# PowerSupply.net
KiCad netlist of a schematic drawn in Altium Designer
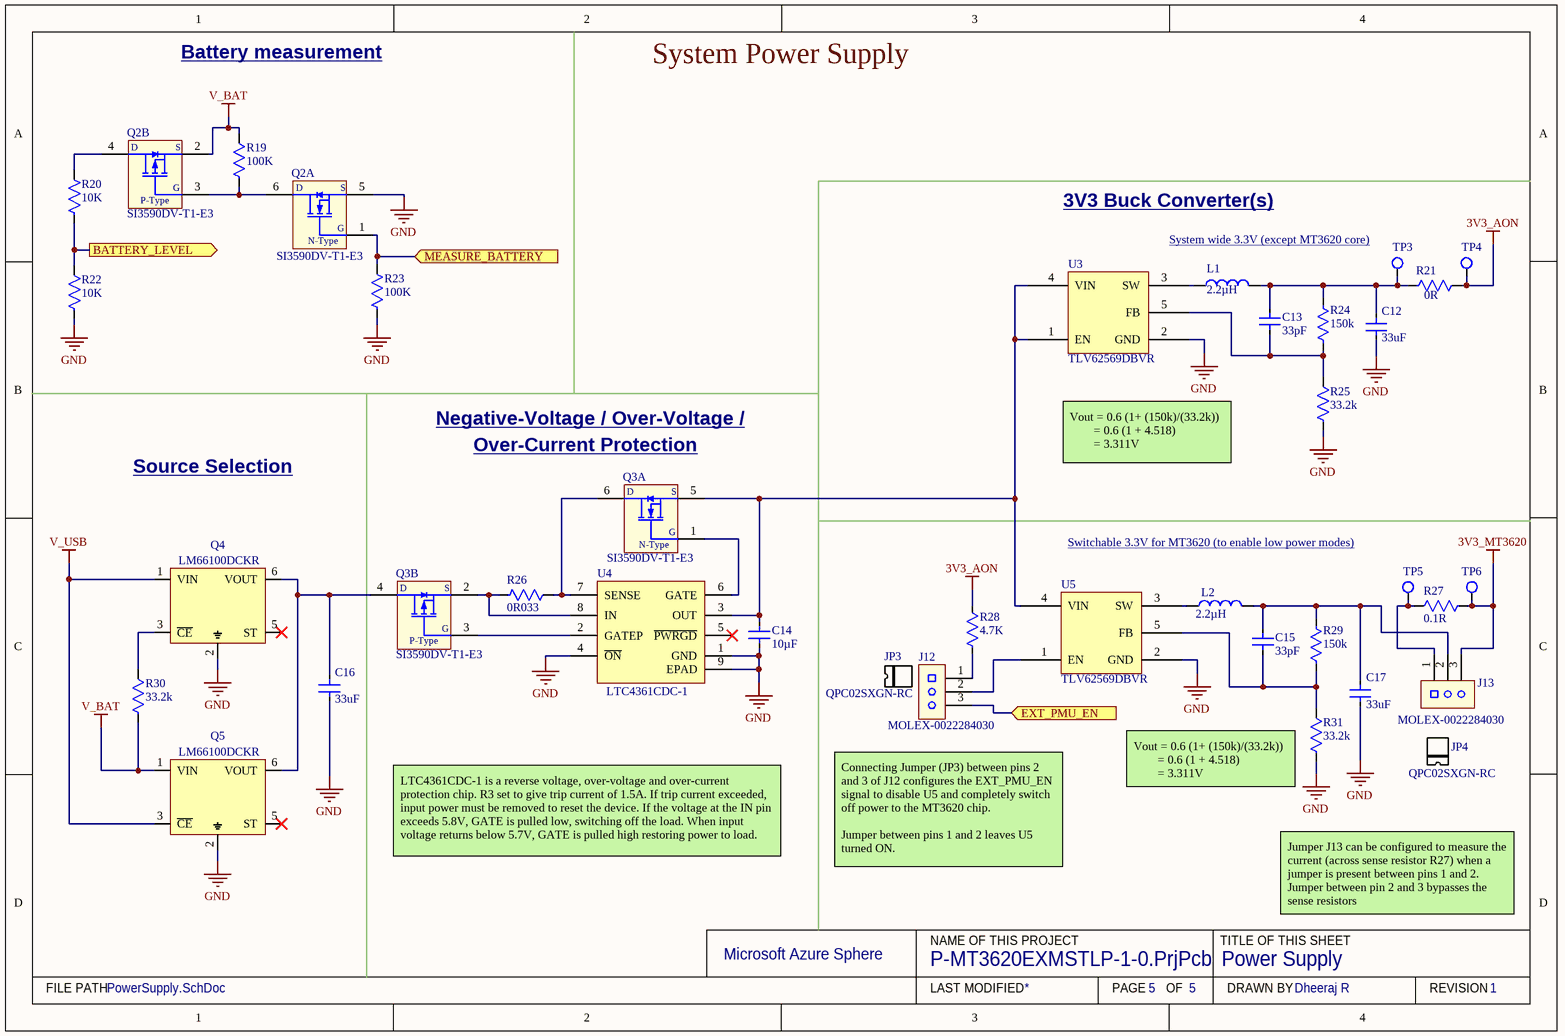
[diagram p0: PowerSupply.SchDoc]

(export (version "E")
  (design (tool "Eeschema 10.0.6"))
  (components
    (comp (ref "C12")
      (value "33uF")
      (footprint "TDK_0805")
      (description "CAP CER 33UF 10V X5R 0805")
      (fields
        (field (name "MANUFACTURER") "TDK")
        (field (name "MANUFACTURER PART NUMBER") "C2012X5R1A336M125AC")
      )
      (libsource (lib "TDK_Capacitor_C_0805") (part "33uF 0805 X5R 10V"))
    )
    (comp (ref "C13")
      (value "33pF")
      (footprint "0603_AVX")
      (fields
        (field (name "MANUFACTURER") "Kyocera AVX")
        (field (name "MANUFACTURER PART NUMBER") "0603YC330JAT2A")
        (field (name "TOLERANCE") "5%")
      )
      (libsource (lib "AVX") (part "0603YC330JAT2A"))
    )
    (comp (ref "C14")
      (value "10µF")
      (footprint "CAPC1608-EIA0603-1MM-MED")
      (description "CAP CER 10UF 25V 20% X5R 0603")
      (fields
        (field (name "MANUFACTURER") "TDK Corporation")
        (field (name "MANUFACTURER PART NUMBER") "C1608X5R1E106M080AC")
        (field (name "CAPACITANCE") "10µF")
      )
      (libsource (lib "TDK-Capacitor_C_0603") (part "10µF 0603 X5R 25V"))
    )
    (comp (ref "C15")
      (value "33pF")
      (footprint "0603_AVX")
      (fields
        (field (name "MANUFACTURER") "Kyocera AVX")
        (field (name "MANUFACTURER PART NUMBER") "0603YC330JAT2A")
        (field (name "TOLERANCE") "5%")
      )
      (libsource (lib "AVX") (part "0603YC330JAT2A"))
    )
    (comp (ref "C16")
      (value "33uF")
      (footprint "TDK_0805")
      (description "CAP CER 33UF 10V X5R 0805")
      (fields
        (field (name "MANUFACTURER") "TDK")
        (field (name "MANUFACTURER PART NUMBER") "C2012X5R1A336M125AC")
      )
      (libsource (lib "TDK_Capacitor_C_0805") (part "33uF 0805 X5R 10V"))
    )
    (comp (ref "C17")
      (value "33uF")
      (footprint "TDK_0805")
      (description "CAP CER 33UF 10V X5R 0805")
      (fields
        (field (name "MANUFACTURER") "TDK")
        (field (name "MANUFACTURER PART NUMBER") "C2012X5R1A336M125AC")
      )
      (libsource (lib "TDK_Capacitor_C_0805") (part "33uF 0805 X5R 10V"))
    )
    (comp (ref "J12")
      (value "MOLEX-0022284030")
      (footprint "0022284030")
      (description "CONN HEADER 3POS .100 VERT TIN")
      (fields
        (field (name "MANUFACTURER") "Molex, LLC")
        (field (name "MANUFACTURER PART NUMBER") "0022284030")
      )
      (libsource (lib "") (part "MOLEX-0022284030_1"))
    )
    (comp (ref "J13")
      (value "MOLEX-0022284030")
      (footprint "0022284030")
      (description "CONN HEADER 3POS .100 VERT TIN")
      (fields
        (field (name "MANUFACTURER") "Molex, LLC")
        (field (name "MANUFACTURER PART NUMBER") "0022284030")
      )
      (libsource (lib "Molex") (part "MOLEX-0022284030"))
    )
    (comp (ref "JP3")
      (value "QPC02SXGN-RC")
      (description "CONN JUMPER SHORTING .100\" GOLD")
      (fields (field (name "MANUFACTURER") "Sullins"))
      (libsource (lib "SullinsConnectorSolutions") (part "QPC02SXGN-RC"))
    )
    (comp (ref "JP4")
      (value "QPC02SXGN-RC")
      (description "CONN JUMPER SHORTING .100\" GOLD")
      (fields (field (name "MANUFACTURER") "Sullins"))
      (libsource (lib "SullinsConnectorSolutions") (part "QPC02SXGN-RC"))
    )
    (comp (ref "L1")
      (value "2.2µH")
      (footprint "NR3015T2R2M")
      (description "FIXED IND 2.2UH 1.5A 72 MOHM SMD")
      (fields
        (field (name "MANUFACTURER") "Taiyo Yuden")
        (field (name "MANUFACTURER PART NUMBER") "NR3015T2R2M")
      )
      (libsource (lib "TaiyoYuden ") (part "NR3015T2R2M"))
    )
    (comp (ref "L2")
      (value "2.2µH")
      (footprint "NR3015T2R2M")
      (description "FIXED IND 2.2UH 1.5A 72 MOHM SMD")
      (fields
        (field (name "MANUFACTURER") "Taiyo Yuden")
        (field (name "MANUFACTURER PART NUMBER") "NR3015T2R2M")
      )
      (libsource (lib "TaiyoYuden ") (part "NR3015T2R2M"))
    )
    (comp (ref "Q2")
      (value "SI3590DV-T1-E3")
      (footprint "SI3590DV-T1-E3")
      (description "MOSFET N&P-CH 30V (D-S)")
      (fields (field (name "MANUFACTURER") "Vishay Siliconix"))
      (libsource (lib "Vishay") (part "SI3590DV-T1-E3"))
    )
    (comp (ref "Q3")
      (value "SI3590DV-T1-E3")
      (footprint "SI3590DV-T1-E3")
      (description "MOSFET N&P-CH 30V (D-S)")
      (fields (field (name "MANUFACTURER") "Vishay Siliconix"))
      (libsource (lib "Vishay") (part "SI3590DV-T1-E3"))
    )
    (comp (ref "Q4")
      (value "LM66100DCKR")
      (footprint "TI-LM6610-SC-70")
      (description "1.5-V to 5.5-V, 1.5-A, 0.5-uA IQ ideal diode with Integrated FET 6-SC70 -40 to 105")
      (fields (field (name "MANUFACTURER") "Texas Instruments"))
      (libsource (lib "TexasInstruments") (part "LM66100DCKR"))
    )
    (comp (ref "Q5")
      (value "LM66100DCKR")
      (footprint "TI-LM6610-SC-70")
      (description "1.5-V to 5.5-V, 1.5-A, 0.5-uA IQ ideal diode with Integrated FET 6-SC70 -40 to 105")
      (fields (field (name "MANUFACTURER") "Texas Instruments"))
      (libsource (lib "TexasInstruments") (part "LM66100DCKR"))
    )
    (comp (ref "R19")
      (value "100K")
      (footprint "VISHAY-0603")
      (description "100K Ohm 0603 1% 0.1W(1/10W) 100ppm Paper T/R")
      (fields
        (field (name "MANUFACTURER") "Yageo")
        (field (name "MANUFACTURER PART NUMBER") "RC0603FR-07100KL")
      )
      (libsource (lib "Yageo") (part "RC0603FR-07100KL"))
    )
    (comp (ref "R20")
      (value "10K")
      (footprint "VISHAY-0603")
      (description "10K Ohm 0603 1% 1/10W ±100ppm/°C Molded SMD Paper T/R")
      (fields
        (field (name "MANUFACTURER") "Yageo")
        (field (name "MANUFACTURER PART NUMBER") "RC0603FR-0710KL")
      )
      (libsource (lib "Yageo") (part "RC0603FR-0710KL"))
    )
    (comp (ref "R21")
      (value "0R")
      (footprint "1608-EIA0603")
      (description "YAGEO         RC0603JR-070RL             RES, THICK FILM, 0R, 0.1W, 0603")
      (fields
        (field (name "MANUFACTURER") "Yageo")
        (field (name "MANUFACTURER PART NUMBER") "RC0603JR-070RL")
      )
      (libsource (lib "Yageo") (part "RC0603JR-070RL"))
    )
    (comp (ref "R22")
      (value "10K")
      (footprint "VISHAY-0603")
      (description "10K Ohm 0603 1% 1/10W ±100ppm/°C Molded SMD Paper T/R")
      (fields
        (field (name "MANUFACTURER") "Yageo")
        (field (name "MANUFACTURER PART NUMBER") "RC0603FR-0710KL")
      )
      (libsource (lib "Yageo") (part "RC0603FR-0710KL"))
    )
    (comp (ref "R23")
      (value "100K")
      (footprint "VISHAY-0603")
      (description "100K Ohm 0603 1% 0.1W(1/10W) 100ppm Paper T/R")
      (fields
        (field (name "MANUFACTURER") "Yageo")
        (field (name "MANUFACTURER PART NUMBER") "RC0603FR-07100KL")
      )
      (libsource (lib "Yageo") (part "RC0603FR-07100KL"))
    )
    (comp (ref "R24")
      (value "150k")
      (footprint "RC0603")
      (fields
        (field (name "MANUFACTURER") "Yageo")
        (field (name "MANUFACTURER PART NUMBER") "RC0603FR-07150KL")
        (field (name "TOLERANCE") "1%")
      )
      (libsource (lib "Yageo") (part "RC0603FR-07150KL"))
    )
    (comp (ref "R25")
      (value "33.2k")
      (footprint "RC0603")
      (description "33.2K OHM 1% 1/10W 0603")
      (fields
        (field (name "MANUFACTURER") "Yageo")
        (field (name "MANUFACTURER PART NUMBER") "RC0603FR-0733K2L")
      )
      (libsource (lib "Yageo") (part "RC0603FR-0733K2L"))
    )
    (comp (ref "R26")
      (value "0R033")
      (footprint "RC0603")
      (description "0.033 Ohm 0603 1% 0.1W(1/10W) ±1500ppm/C Epoxy Pad SMD Automotive T/R")
      (fields
        (field (name "MANUFACTURER") "Yageo")
        (field (name "MANUFACTURER PART NUMBER") "RL0603FR-070R033L")
      )
      (libsource (lib "Yageo") (part "RL0603FR-070R033L"))
    )
    (comp (ref "R27")
      (value "0.1R")
      (footprint "VISHAY-0603")
      (description "0.1 Ohm 0603 0.5% 0.20W Current Sense Rohs Compliant: Yes")
      (fields (field (name "MANUFACTURER") "Ohmite") (field (name "MANUFACTURER PART NUMBER") "KDV06DR100ET"))
      (libsource (lib "Ohmite") (part "KDV06DR100ET"))
    )
    (comp (ref "R28")
      (value "4.7K")
      (footprint "RC0603")
      (description "4.7K OHM 0603 1% 1/10W")
      (fields
        (field (name "MANUFACTURER") "Yageo")
        (field (name "MANUFACTURER PART NUMBER") "RC0603FR-074K7L")
      )
      (libsource (lib "Yageo") (part "RC0603FR-074K7L"))
    )
    (comp (ref "R29")
      (value "150k")
      (footprint "RC0603")
      (fields
        (field (name "MANUFACTURER") "Yageo")
        (field (name "MANUFACTURER PART NUMBER") "RC0603FR-07150KL")
        (field (name "TOLERANCE") "1%")
      )
      (libsource (lib "Yageo") (part "RC0603FR-07150KL"))
    )
    (comp (ref "R30")
      (value "33.2k")
      (footprint "RC0603")
      (description "33.2K OHM 1% 1/10W 0603")
      (fields
        (field (name "MANUFACTURER") "Yageo")
        (field (name "MANUFACTURER PART NUMBER") "RC0603FR-0733K2L")
      )
      (libsource (lib "Yageo") (part "RC0603FR-0733K2L"))
    )
    (comp (ref "R31")
      (value "33.2k")
      (footprint "RC0603")
      (description "33.2K OHM 1% 1/10W 0603")
      (fields
        (field (name "MANUFACTURER") "Yageo")
        (field (name "MANUFACTURER PART NUMBER") "RC0603FR-0733K2L")
      )
      (libsource (lib "Yageo") (part "RC0603FR-0733K2L"))
    )
    (comp (ref "TP3")
      (value "TestPointHole")
      (footprint "PTH1.27mm-0.9mm")
      (description "Test Point With Hole")
      (libsource (lib "generic") (part "TestPointHole"))
    )
    (comp (ref "TP4")
      (value "TestPointHole")
      (footprint "PTH1.27mm-0.9mm")
      (description "Test Point With Hole")
      (libsource (lib "generic") (part "TestPointHole"))
    )
    (comp (ref "TP5")
      (value "TestPointHole")
      (footprint "PTH1.27mm-0.9mm")
      (description "Test Point With Hole")
      (libsource (lib "generic") (part "TestPointHole"))
    )
    (comp (ref "TP6")
      (value "TestPointHole")
      (footprint "PTH1.27mm-0.9mm")
      (description "Test Point With Hole")
      (libsource (lib "generic") (part "TestPointHole"))
    )
    (comp (ref "U3")
      (value "TLV62569DBVR")
      (footprint "TI-SOT23-6")
      (description "Variable voltage buck converter")
      (fields (field (name "MANUFACTURER") "Texas Instruments"))
      (libsource (lib "TexasInstruments") (part "TLV62569DBVR"))
    )
    (comp (ref "U4")
      (value "LTC4361CDC-1")
      (footprint "LTC4361-1#TRPBF")
      (description "LINEAR TECHNOLOGY LTC4361CDC-1#TRMPBF IC, OVERVOLTAGE/CUR PROT, 8DFN")
      (fields
        (field (name "MANUFACTURER") "Linear Technology")
        (field (name "MANUFACTURER PART NUMBER") "LTC4361CDC-1#TRMPBF")
      )
      (libsource (lib "LinearTech") (part "LTC4361CDC-1#TRMPBF"))
    )
    (comp (ref "U5")
      (value "TLV62569DBVR")
      (footprint "TI-SOT23-6")
      (description "Variable voltage buck converter")
      (fields (field (name "MANUFACTURER") "Texas Instruments"))
      (libsource (lib "TexasInstruments") (part "TLV62569DBVR"))
    )
  )
  (nets
    (net (code "1") (name "/BATTERY_LEVEL") (class "Default")
      (node (ref "R20") (pin "1") (pinfunction "1_1") (pintype "passive"))
      (node (ref "R22") (pin "2") (pinfunction "2_2") (pintype "passive"))
    )
    (net (code "2") (name "/EXT_PMU_EN") (class "Default")
      (node (ref "J12") (pin "3") (pinfunction "3_3") (pintype "passive"))
    )
    (net (code "3") (name "/MEASURE_BATTERY") (class "Default")
      (node (ref "Q2") (pin "1") (pinfunction "G1_1") (pintype "passive"))
      (node (ref "R23") (pin "2") (pinfunction "2_2") (pintype "passive"))
    )
    (net (code "4") (name "3V3_AON") (class "Default")
      (node (ref "R21") (pin "2") (pinfunction "2_2") (pintype "passive"))
      (node (ref "R28") (pin "2") (pinfunction "2_2") (pintype "passive"))
      (node (ref "TP4") (pin "1") (pinfunction "1_1") (pintype "passive"))
    )
    (net (code "5") (name "3V3_MT3620") (class "Default")
      (node (ref "J13") (pin "3") (pinfunction "3_3") (pintype "passive"))
      (node (ref "R27") (pin "2") (pinfunction "2_2") (pintype "passive"))
      (node (ref "TP6") (pin "1") (pinfunction "1_1") (pintype "passive"))
    )
    (net (code "6") (name "GND") (class "Default")
      (node (ref "C12") (pin "1") (pinfunction "1_1") (pintype "passive"))
      (node (ref "C14") (pin "1") (pinfunction "1_1") (pintype "passive"))
      (node (ref "C16") (pin "1") (pinfunction "1_1") (pintype "passive"))
      (node (ref "C17") (pin "1") (pinfunction "1_1") (pintype "passive"))
      (node (ref "Q2") (pin "5") (pinfunction "S1_5") (pintype "passive"))
      (node (ref "Q4") (pin "2") (pinfunction "GND_2") (pintype "passive"))
      (node (ref "Q5") (pin "2") (pinfunction "GND_2") (pintype "passive"))
      (node (ref "R22") (pin "1") (pinfunction "1_1") (pintype "passive"))
      (node (ref "R23") (pin "1") (pinfunction "1_1") (pintype "passive"))
      (node (ref "R25") (pin "1") (pinfunction "1_1") (pintype "passive"))
      (node (ref "R31") (pin "1") (pinfunction "1_1") (pintype "passive"))
      (node (ref "U3") (pin "2") (pinfunction "GND_2") (pintype "passive"))
      (node (ref "U4") (pin "1") (pinfunction "GND_1") (pintype "passive"))
      (node (ref "U4") (pin "4") (pinfunction "~{ON}_4") (pintype "passive"))
      (node (ref "U4") (pin "9") (pinfunction "EPAD_9") (pintype "passive"))
      (node (ref "U5") (pin "2") (pinfunction "GND_2") (pintype "passive"))
    )
    (net (code "7") (name "Net-(C12-Pad2)") (class "Default")
      (node (ref "C12") (pin "2") (pinfunction "2_2") (pintype "passive"))
      (node (ref "C13") (pin "2") (pinfunction "2_2") (pintype "passive"))
      (node (ref "L1") (pin "2") (pinfunction "2_2") (pintype "passive"))
      (node (ref "R21") (pin "1") (pinfunction "1_1") (pintype "passive"))
      (node (ref "R24") (pin "2") (pinfunction "2_2") (pintype "passive"))
      (node (ref "TP3") (pin "1") (pinfunction "1_1") (pintype "passive"))
    )
    (net (code "8") (name "Net-(C15-Pad2)") (class "Default")
      (node (ref "C15") (pin "2") (pinfunction "2_2") (pintype "passive"))
      (node (ref "C17") (pin "2") (pinfunction "2_2") (pintype "passive"))
      (node (ref "J13") (pin "2") (pinfunction "2_2") (pintype "passive"))
      (node (ref "L2") (pin "2") (pinfunction "2_2") (pintype "passive"))
      (node (ref "R29") (pin "2") (pinfunction "2_2") (pintype "passive"))
    )
    (net (code "9") (name "Net-(J12-Pad1)") (class "Default")
      (node (ref "J12") (pin "1") (pinfunction "1_1") (pintype "passive"))
      (node (ref "R28") (pin "1") (pinfunction "1_1") (pintype "passive"))
    )
    (net (code "10") (name "Net-(J13-Pad1)") (class "Default")
      (node (ref "J13") (pin "1") (pinfunction "1_1") (pintype "passive"))
      (node (ref "R27") (pin "1") (pinfunction "1_1") (pintype "passive"))
      (node (ref "TP5") (pin "1") (pinfunction "1_1") (pintype "passive"))
    )
    (net (code "11") (name "Net-(Q2A-D1)") (class "Default")
      (node (ref "Q2") (pin "3") (pinfunction "G2_3") (pintype "passive"))
      (node (ref "Q2") (pin "6") (pinfunction "D1_6") (pintype "passive"))
      (node (ref "R19") (pin "1") (pinfunction "1_1") (pintype "passive"))
    )
    (net (code "12") (name "Net-(Q2B-D2)") (class "Default")
      (node (ref "Q2") (pin "4") (pinfunction "D2_4") (pintype "passive"))
      (node (ref "R20") (pin "2") (pinfunction "2_2") (pintype "passive"))
    )
    (net (code "13") (name "Net-(Q3A-D1)") (class "Default")
      (node (ref "Q3") (pin "6") (pinfunction "D1_6") (pintype "passive"))
      (node (ref "R26") (pin "2") (pinfunction "2_2") (pintype "passive"))
      (node (ref "U4") (pin "7") (pinfunction "SENSE_7") (pintype "passive"))
    )
    (net (code "14") (name "Net-(Q3A-G1)") (class "Default")
      (node (ref "Q3") (pin "1") (pinfunction "G1_1") (pintype "passive"))
      (node (ref "U4") (pin "6") (pinfunction "GATE_6") (pintype "passive"))
    )
    (net (code "15") (name "Net-(Q3A-S1)") (class "Default")
      (node (ref "C14") (pin "2") (pinfunction "2_2") (pintype "passive"))
      (node (ref "Q3") (pin "5") (pinfunction "S1_5") (pintype "passive"))
      (node (ref "U3") (pin "1") (pinfunction "EN_1") (pintype "passive"))
      (node (ref "U3") (pin "4") (pinfunction "VIN_4") (pintype "passive"))
      (node (ref "U4") (pin "3") (pinfunction "OUT_3") (pintype "passive"))
      (node (ref "U5") (pin "4") (pinfunction "VIN_4") (pintype "passive"))
    )
    (net (code "16") (name "Net-(Q3B-D2)") (class "Default")
      (node (ref "C16") (pin "2") (pinfunction "2_2") (pintype "passive"))
      (node (ref "Q3") (pin "4") (pinfunction "D2_4") (pintype "passive"))
      (node (ref "Q4") (pin "6") (pinfunction "VOUT_6") (pintype "passive"))
      (node (ref "Q5") (pin "6") (pinfunction "VOUT_6") (pintype "passive"))
    )
    (net (code "17") (name "Net-(Q3B-G2)") (class "Default")
      (node (ref "Q3") (pin "3") (pinfunction "G2_3") (pintype "passive"))
      (node (ref "U4") (pin "2") (pinfunction "GATEP_2") (pintype "passive"))
    )
    (net (code "18") (name "Net-(Q3B-S2)") (class "Default")
      (node (ref "Q3") (pin "2") (pinfunction "S2_2") (pintype "passive"))
      (node (ref "R26") (pin "1") (pinfunction "1_1") (pintype "passive"))
      (node (ref "U4") (pin "8") (pinfunction "IN_8") (pintype "passive"))
    )
    (net (code "19") (name "Net-(Q4-~{CE})") (class "Default")
      (node (ref "Q4") (pin "3") (pinfunction "~{CE}_3") (pintype "passive"))
      (node (ref "R30") (pin "2") (pinfunction "2_2") (pintype "passive"))
    )
    (net (code "20") (name "Net-(U3-FB)") (class "Default")
      (node (ref "C13") (pin "1") (pinfunction "1_1") (pintype "passive"))
      (node (ref "R24") (pin "1") (pinfunction "1_1") (pintype "passive"))
      (node (ref "R25") (pin "2") (pinfunction "2_2") (pintype "passive"))
      (node (ref "U3") (pin "5") (pinfunction "FB_5") (pintype "passive"))
    )
    (net (code "21") (name "Net-(U3-SW)") (class "Default")
      (node (ref "L1") (pin "1") (pinfunction "1_1") (pintype "passive"))
      (node (ref "U3") (pin "3") (pinfunction "SW_3") (pintype "passive"))
    )
    (net (code "22") (name "Net-(U5-EN)") (class "Default")
      (node (ref "J12") (pin "2") (pinfunction "2_2") (pintype "passive"))
      (node (ref "U5") (pin "1") (pinfunction "EN_1") (pintype "passive"))
    )
    (net (code "23") (name "Net-(U5-FB)") (class "Default")
      (node (ref "C15") (pin "1") (pinfunction "1_1") (pintype "passive"))
      (node (ref "R29") (pin "1") (pinfunction "1_1") (pintype "passive"))
      (node (ref "R31") (pin "2") (pinfunction "2_2") (pintype "passive"))
      (node (ref "U5") (pin "5") (pinfunction "FB_5") (pintype "passive"))
    )
    (net (code "24") (name "Net-(U5-SW)") (class "Default")
      (node (ref "L2") (pin "1") (pinfunction "1_1") (pintype "passive"))
      (node (ref "U5") (pin "3") (pinfunction "SW_3") (pintype "passive"))
    )
    (net (code "25") (name "V_BAT") (class "Default")
      (node (ref "Q2") (pin "2") (pinfunction "S2_2") (pintype "passive"))
      (node (ref "Q5") (pin "1") (pinfunction "VIN_1") (pintype "passive"))
      (node (ref "R19") (pin "2") (pinfunction "2_2") (pintype "passive"))
      (node (ref "R30") (pin "1") (pinfunction "1_1") (pintype "passive"))
    )
    (net (code "26") (name "V_USB") (class "Default")
      (node (ref "Q4") (pin "1") (pinfunction "VIN_1") (pintype "passive"))
      (node (ref "Q5") (pin "3") (pinfunction "~{CE}_3") (pintype "passive"))
    )
    (net (code "27") (name "unconnected-(Q4-NC-Pad4)") (class "Default")
      (node (ref "Q4") (pin "4") (pinfunction "NC_4") (pintype "passive"))
    )
    (net (code "28") (name "unconnected-(Q4-ST-Pad5)") (class "Default")
      (node (ref "Q4") (pin "5") (pinfunction "ST_5") (pintype "passive+no_connect"))
    )
    (net (code "29") (name "unconnected-(Q5-NC-Pad4)") (class "Default")
      (node (ref "Q5") (pin "4") (pinfunction "NC_4") (pintype "passive"))
    )
    (net (code "30") (name "unconnected-(Q5-ST-Pad5)") (class "Default")
      (node (ref "Q5") (pin "5") (pinfunction "ST_5") (pintype "passive+no_connect"))
    )
    (net (code "31") (name "unconnected-(U4-~{PWRGD}-Pad5)") (class "Default")
      (node (ref "U4") (pin "5") (pinfunction "~{PWRGD}_5") (pintype "passive+no_connect"))
    )
  )
)
